# SubHarmonics_Main_Board_v1.net
KiCad netlist of a schematic drawn in EAGLE
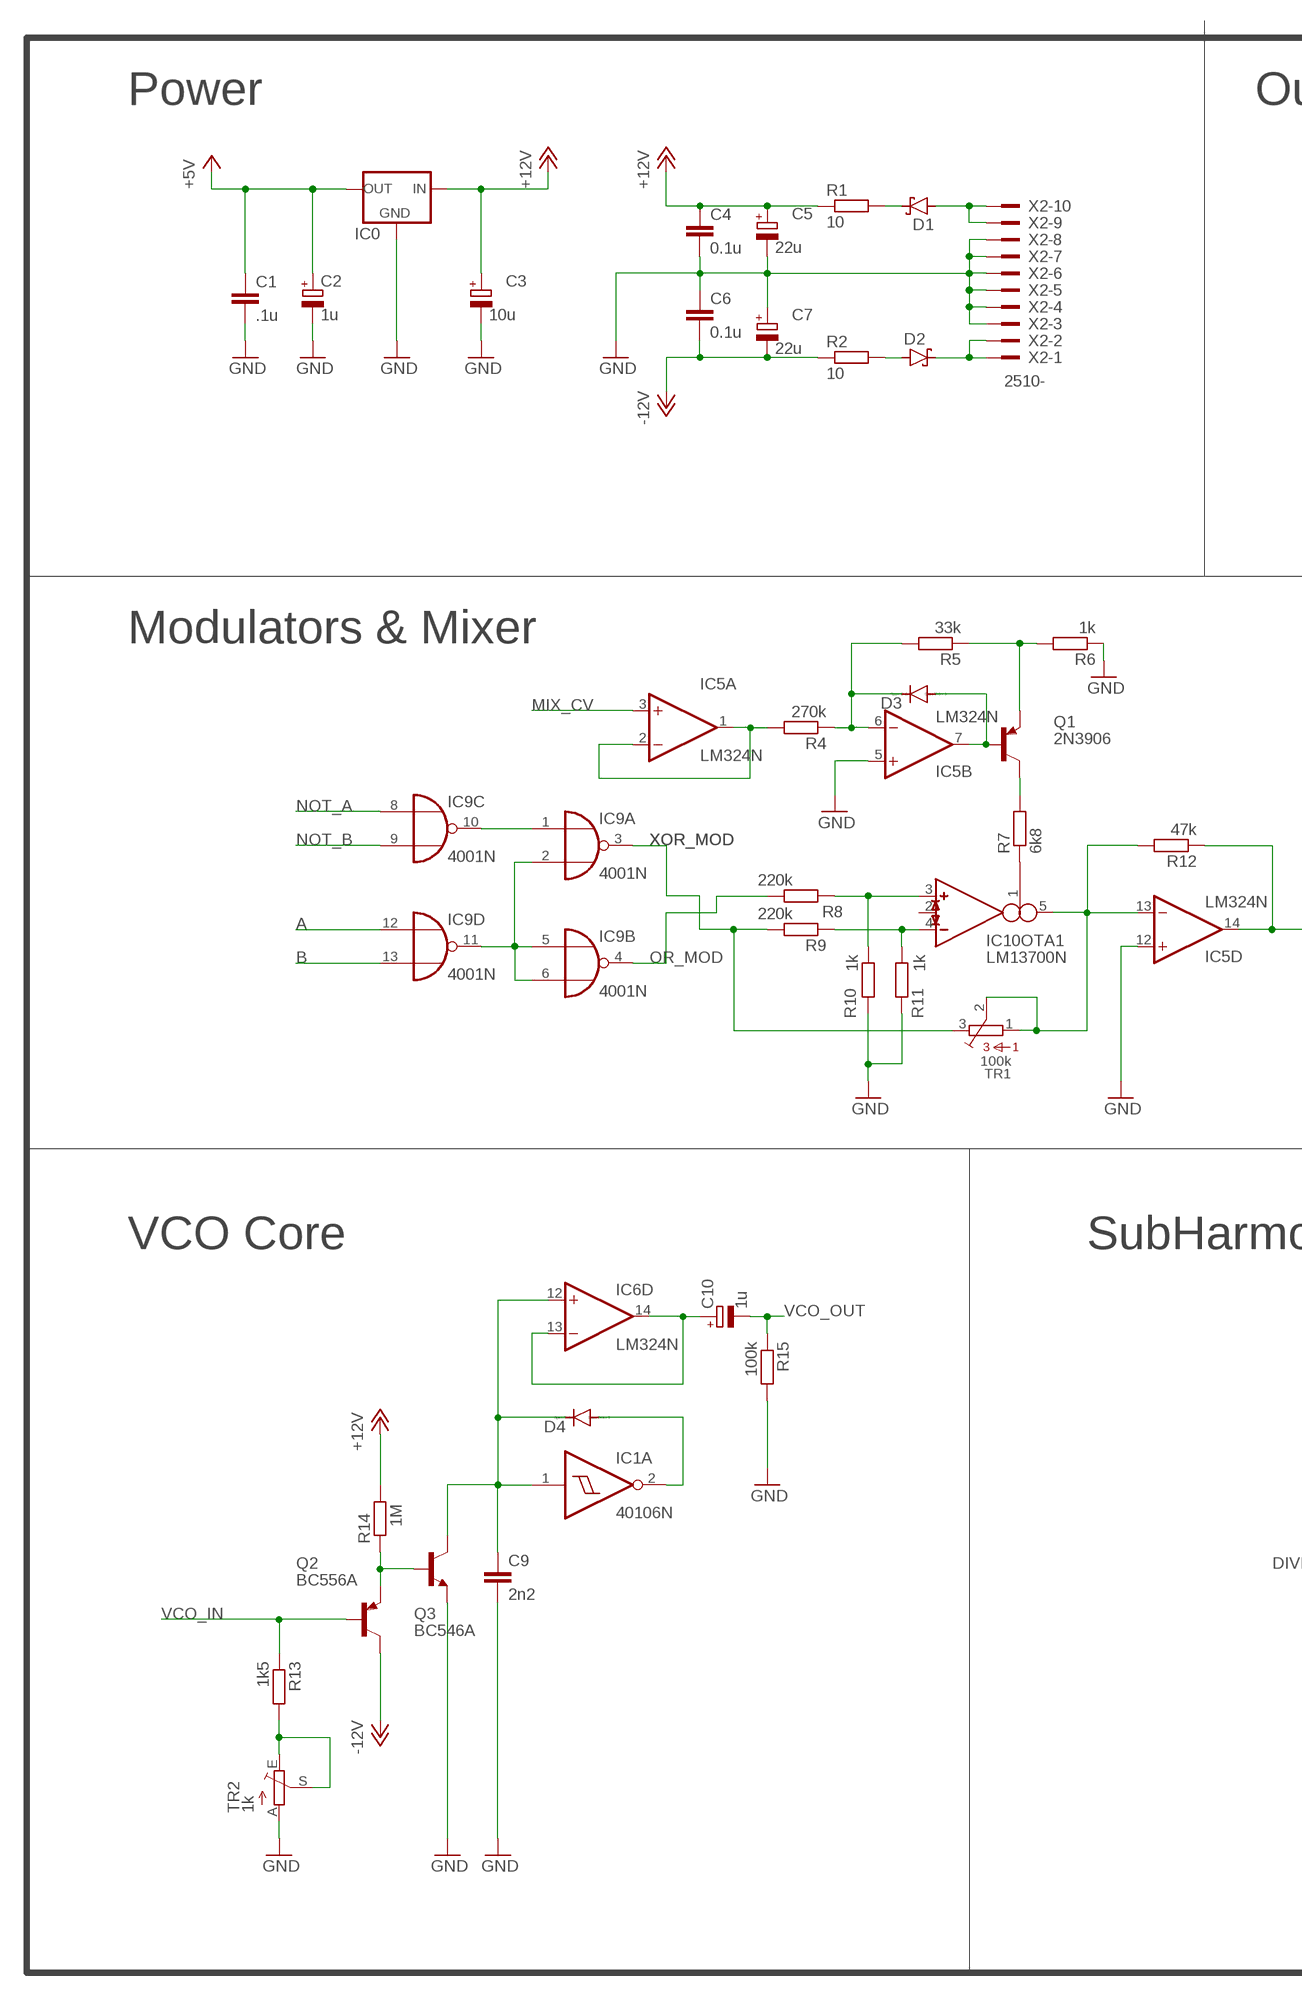
[diagram p0: schematic, sheet 1, part 1 of 2]
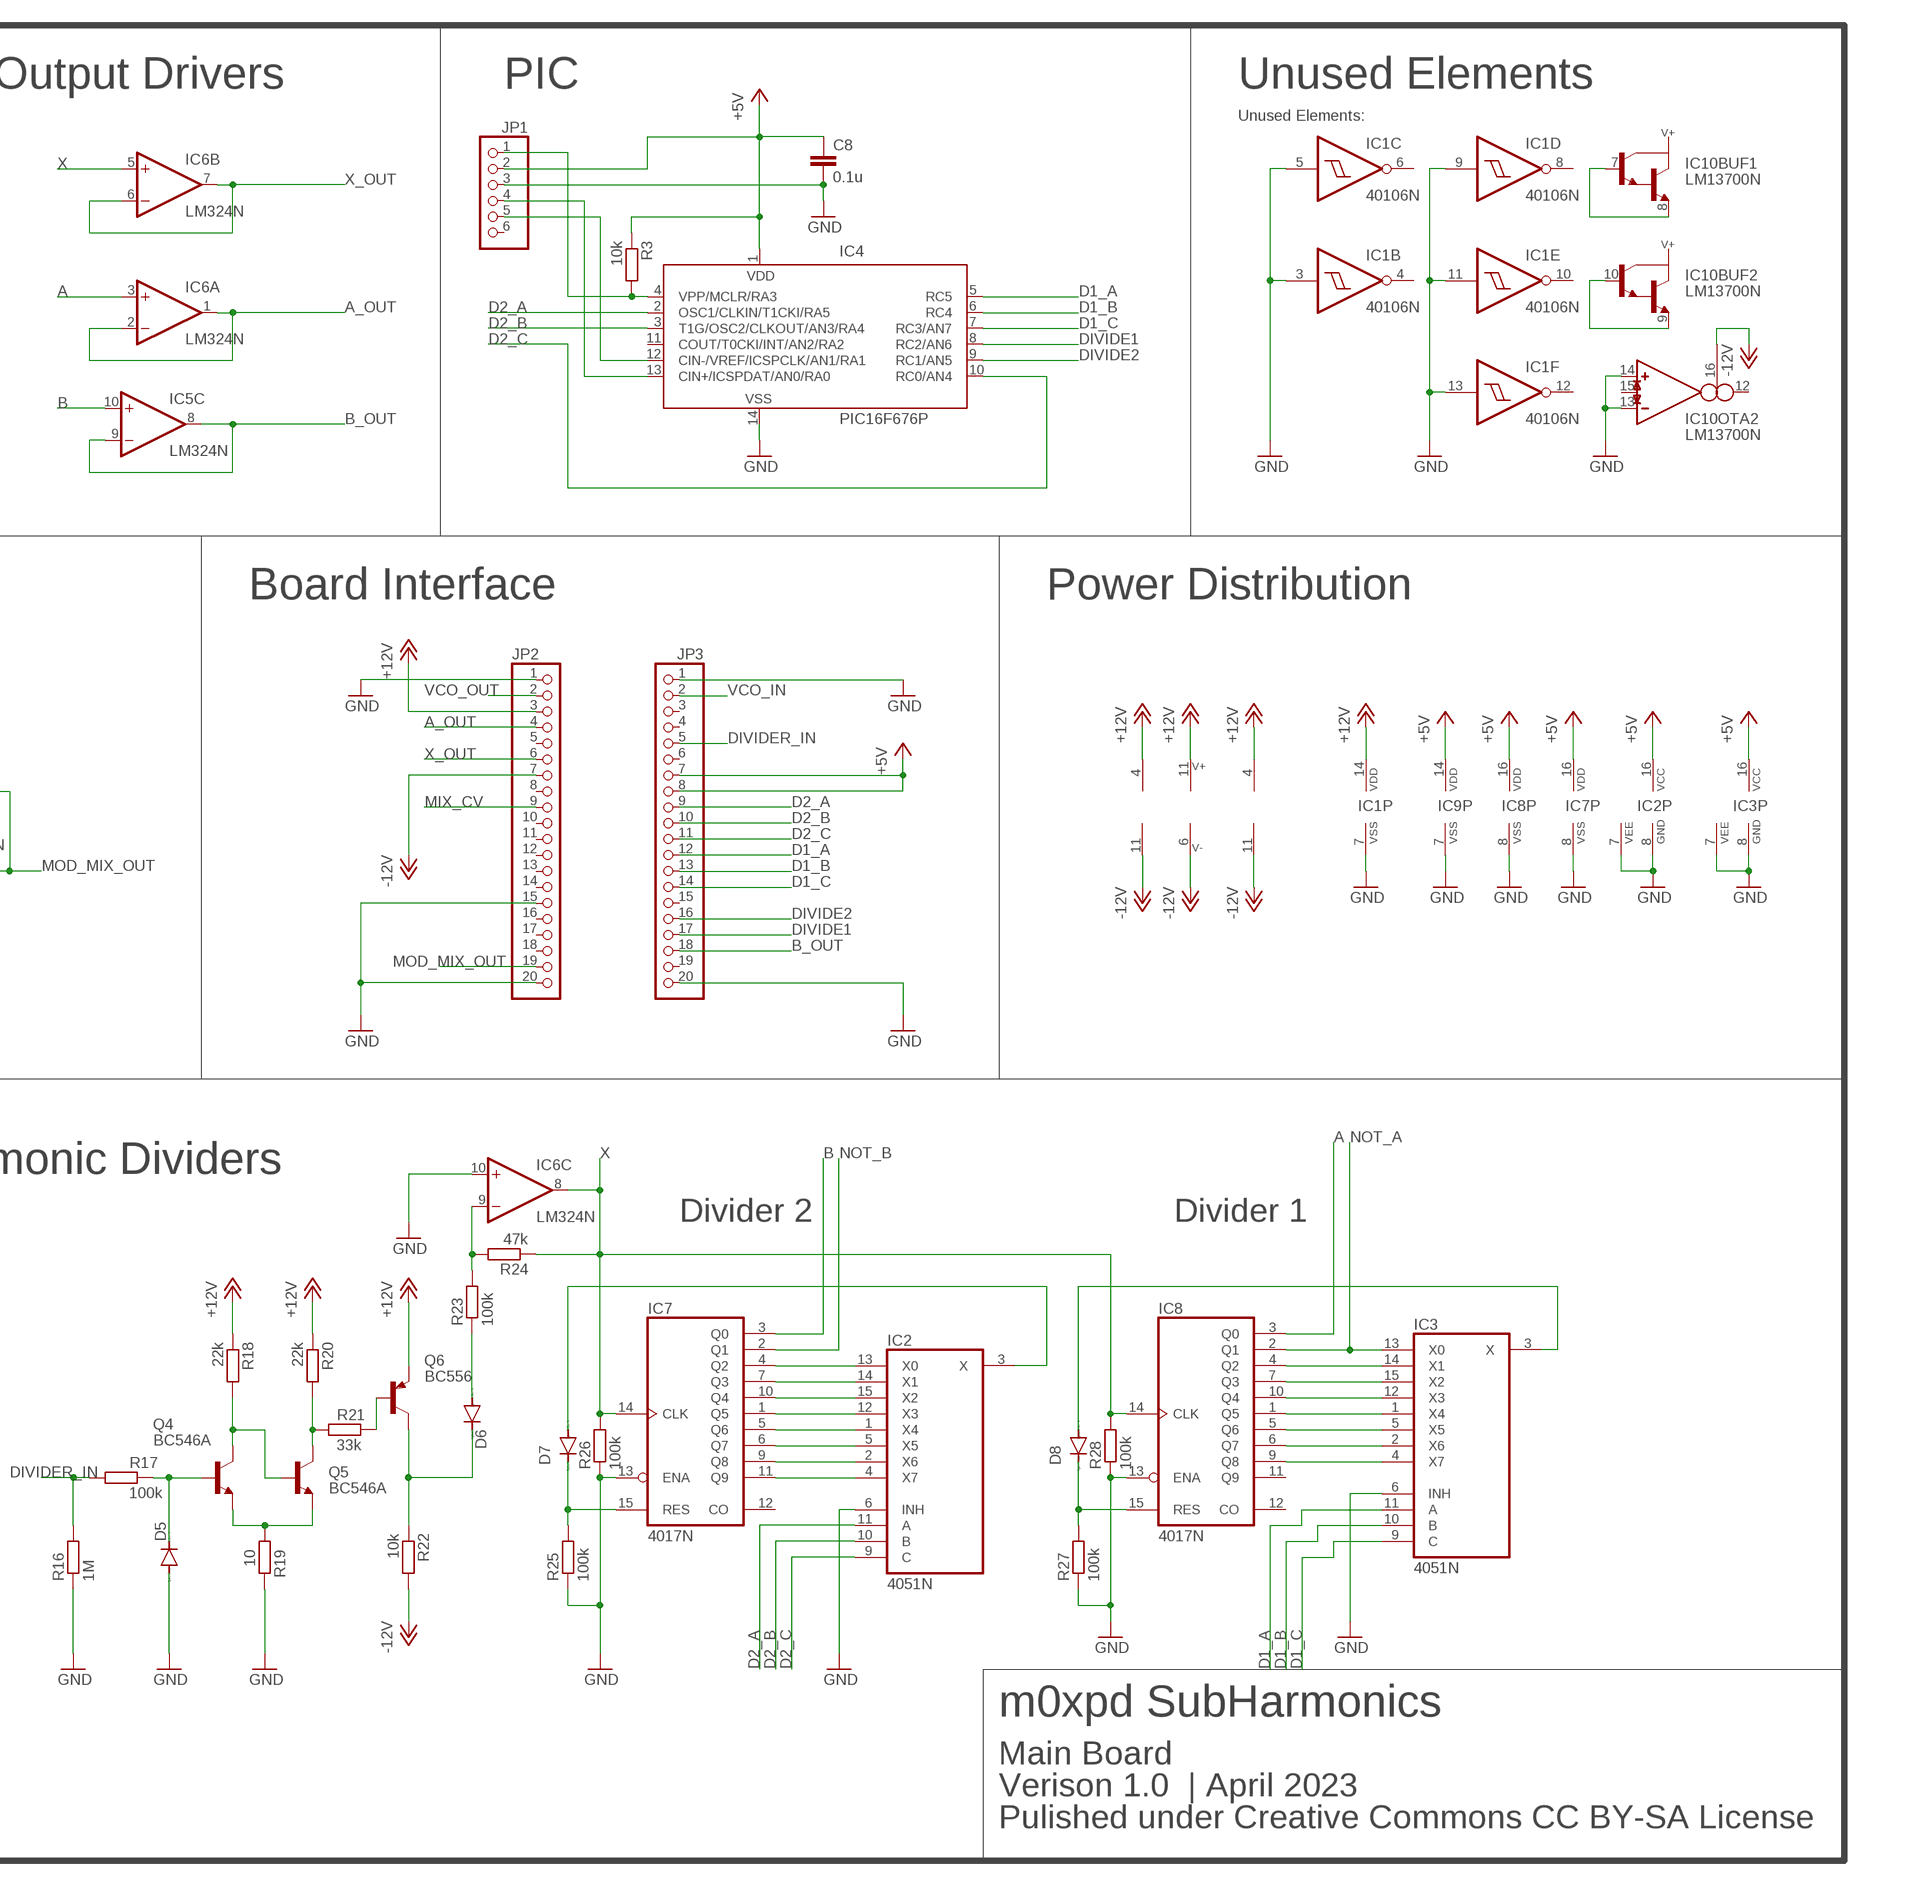
[diagram p1: schematic, sheet 1, part 2 of 2]

(export (version "E")
  (design (tool "Eeschema 10.0.6"))
  (components
    (comp (ref "C1")
      (value ".1u")
      (footprint "eagle-import:C050-025X075")
      (libsource (lib "eagle-import") (part "C-EU050-025X075"))
    )
    (comp (ref "C2")
      (value "1u")
      (footprint "eagle-import:E2,5-5")
      (libsource (lib "eagle-import") (part "CPOL-EUE2.5-5"))
    )
    (comp (ref "C3")
      (value "10u")
      (footprint "eagle-import:E2,5-5")
      (libsource (lib "eagle-import") (part "CPOL-EUE2.5-5"))
    )
    (comp (ref "C4")
      (value "0.1u")
      (footprint "eagle-import:C050-025X075")
      (libsource (lib "eagle-import") (part "C-EU050-025X075"))
    )
    (comp (ref "C5")
      (value "22u")
      (footprint "eagle-import:E2,5-5")
      (libsource (lib "eagle-import") (part "CPOL-EUE2.5-5"))
    )
    (comp (ref "C6")
      (value "0.1u")
      (footprint "eagle-import:C050-025X075")
      (libsource (lib "eagle-import") (part "C-EU050-025X075"))
    )
    (comp (ref "C7")
      (value "22u")
      (footprint "eagle-import:E2,5-5")
      (libsource (lib "eagle-import") (part "CPOL-EUE2.5-5"))
    )
    (comp (ref "C8")
      (value "0.1u")
      (footprint "eagle-import:C050-025X075")
      (libsource (lib "eagle-import") (part "C-EU050-025X075"))
    )
    (comp (ref "C9")
      (value "2n2")
      (footprint "eagle-import:C050-030X075")
      (libsource (lib "eagle-import") (part "C-EU050-030X075"))
    )
    (comp (ref "C10")
      (value "1u")
      (footprint "eagle-import:E2,5-5")
      (libsource (lib "eagle-import") (part "CPOL-EUE2.5-5"))
    )
    (comp (ref "D1")
      (value "SCHOTTKY-DIODEDO35-7")
      (footprint "eagle-import:DO35-7")
      (libsource (lib "eagle-import") (part "SCHOTTKY-DIODEDO35-7"))
    )
    (comp (ref "D2")
      (value "SCHOTTKY-DIODEDO35-7")
      (footprint "eagle-import:DO35-7")
      (libsource (lib "eagle-import") (part "SCHOTTKY-DIODEDO35-7"))
    )
    (comp (ref "D3")
      (value "1N4148DO35-7")
      (footprint "eagle-import:DO35-7")
      (libsource (lib "eagle-import") (part "1N4148DO35-7"))
    )
    (comp (ref "D4")
      (value "1N4148DO35-7")
      (footprint "eagle-import:DO35-7")
      (libsource (lib "eagle-import") (part "1N4148DO35-7"))
    )
    (comp (ref "D5")
      (value "1N4148DO35-7")
      (footprint "eagle-import:DO35-7")
      (libsource (lib "eagle-import") (part "1N4148DO35-7"))
    )
    (comp (ref "D6")
      (value "1N4148DO35-7")
      (footprint "eagle-import:DO35-7")
      (libsource (lib "eagle-import") (part "1N4148DO35-7"))
    )
    (comp (ref "D7")
      (value "1N4148DO35-7")
      (footprint "eagle-import:DO35-7")
      (libsource (lib "eagle-import") (part "1N4148DO35-7"))
    )
    (comp (ref "D8")
      (value "1N4148DO35-7")
      (footprint "eagle-import:DO35-7")
      (libsource (lib "eagle-import") (part "1N4148DO35-7"))
    )
    (comp (ref "IC0")
      (value "78LXX")
      (footprint "eagle-import:78LXX")
      (libsource (lib "eagle-import") (part "78LXX"))
    )
    (comp (ref "IC1")
      (value "40106N")
      (footprint "eagle-import:DIL14")
      (libsource (lib "eagle-import") (part "40106N"))
    )
    (comp (ref "IC2")
      (value "4051N")
      (footprint "eagle-import:DIL16")
      (libsource (lib "eagle-import") (part "4051N"))
    )
    (comp (ref "IC3")
      (value "4051N")
      (footprint "eagle-import:DIL16")
      (libsource (lib "eagle-import") (part "4051N"))
    )
    (comp (ref "IC4")
      (value "PIC16F676P")
      (footprint "eagle-import:DIL14")
      (fields (field (name "MF") "MICROCHIP") (field (name "MPN") "PIC16F676-I/P"))
      (libsource (lib "eagle-import") (part "PIC16F676P"))
    )
    (comp (ref "IC5")
      (value "LM324N")
      (footprint "eagle-import:DIL14")
      (libsource (lib "eagle-import") (part "LM324N"))
    )
    (comp (ref "IC6")
      (value "LM324N")
      (footprint "eagle-import:DIL14")
      (libsource (lib "eagle-import") (part "LM324N"))
    )
    (comp (ref "IC7")
      (value "4017N")
      (footprint "eagle-import:DIL16")
      (libsource (lib "eagle-import") (part "4017N"))
    )
    (comp (ref "IC8")
      (value "4017N")
      (footprint "eagle-import:DIL16")
      (libsource (lib "eagle-import") (part "4017N"))
    )
    (comp (ref "IC9")
      (value "4001N")
      (footprint "eagle-import:DIL14")
      (libsource (lib "eagle-import") (part "4001N"))
    )
    (comp (ref "IC10")
      (value "LM13700N")
      (footprint "eagle-import:DIL16")
      (libsource (lib "eagle-import") (part "LM13700N"))
    )
    (comp (ref "JP1")
      (value "PINHD-1X6")
      (footprint "eagle-import:1X06")
      (libsource (lib "eagle-import") (part "PINHD-1X6"))
    )
    (comp (ref "JP2")
      (value "PINHD-1X20")
      (footprint "eagle-import:1X20")
      (libsource (lib "eagle-import") (part "PINHD-1X20"))
    )
    (comp (ref "JP3")
      (value "PINHD-1X20")
      (footprint "eagle-import:1X20")
      (libsource (lib "eagle-import") (part "PINHD-1X20"))
    )
    (comp (ref "Q1")
      (value "2N3906")
      (footprint "eagle-import:TO92")
      (libsource (lib "eagle-import") (part "2N3906"))
    )
    (comp (ref "Q2")
      (value "BC556A")
      (footprint "eagle-import:TO92-EBC")
      (libsource (lib "eagle-import") (part "BC556A"))
    )
    (comp (ref "Q3")
      (value "BC546A")
      (footprint "eagle-import:TO92-EBC")
      (libsource (lib "eagle-import") (part "BC546A"))
    )
    (comp (ref "Q4")
      (value "BC546A")
      (footprint "eagle-import:TO92-EBC")
      (libsource (lib "eagle-import") (part "BC546A"))
    )
    (comp (ref "Q5")
      (value "BC546A")
      (footprint "eagle-import:TO92-EBC")
      (libsource (lib "eagle-import") (part "BC546A"))
    )
    (comp (ref "Q6")
      (value "BC556")
      (footprint "eagle-import:TO92-EBC")
      (libsource (lib "eagle-import") (part "BC556"))
    )
    (comp (ref "R1")
      (value "10")
      (footprint "eagle-import:0204_7")
      (libsource (lib "eagle-import") (part "R-EU_0204/7"))
    )
    (comp (ref "R2")
      (value "10")
      (footprint "eagle-import:0204_7")
      (libsource (lib "eagle-import") (part "R-EU_0204/7"))
    )
    (comp (ref "R3")
      (value "10k")
      (footprint "eagle-import:0204_7")
      (libsource (lib "eagle-import") (part "R-EU_0204/7"))
    )
    (comp (ref "R4")
      (value "270k")
      (footprint "eagle-import:0204_7")
      (libsource (lib "eagle-import") (part "R-EU_0204/7"))
    )
    (comp (ref "R5")
      (value "33k")
      (footprint "eagle-import:0204_7")
      (libsource (lib "eagle-import") (part "R-EU_0204/7"))
    )
    (comp (ref "R6")
      (value "1k")
      (footprint "eagle-import:0204_7")
      (libsource (lib "eagle-import") (part "R-EU_0204/7"))
    )
    (comp (ref "R7")
      (value "6k8")
      (footprint "eagle-import:0204_7")
      (libsource (lib "eagle-import") (part "R-EU_0204/7"))
    )
    (comp (ref "R8")
      (value "220k")
      (footprint "eagle-import:0204_7")
      (libsource (lib "eagle-import") (part "R-EU_0204/7"))
    )
    (comp (ref "R9")
      (value "220k")
      (footprint "eagle-import:0204_7")
      (libsource (lib "eagle-import") (part "R-EU_0204/7"))
    )
    (comp (ref "R10")
      (value "1k")
      (footprint "eagle-import:0204_7")
      (libsource (lib "eagle-import") (part "R-EU_0204/7"))
    )
    (comp (ref "R11")
      (value "1k")
      (footprint "eagle-import:0204_7")
      (libsource (lib "eagle-import") (part "R-EU_0204/7"))
    )
    (comp (ref "R12")
      (value "47k")
      (footprint "eagle-import:0204_7")
      (libsource (lib "eagle-import") (part "R-EU_0204/7"))
    )
    (comp (ref "R13")
      (value "1k5")
      (footprint "eagle-import:0204_7")
      (libsource (lib "eagle-import") (part "R-EU_0204/7"))
    )
    (comp (ref "R14")
      (value "1M")
      (footprint "eagle-import:0204_7")
      (libsource (lib "eagle-import") (part "R-EU_0204/7"))
    )
    (comp (ref "R15")
      (value "100k")
      (footprint "eagle-import:0204_7")
      (libsource (lib "eagle-import") (part "R-EU_0204/7"))
    )
    (comp (ref "R16")
      (value "1M")
      (footprint "eagle-import:0204_7")
      (libsource (lib "eagle-import") (part "R-EU_0204/7"))
    )
    (comp (ref "R17")
      (value "100k")
      (footprint "eagle-import:0204_7")
      (libsource (lib "eagle-import") (part "R-EU_0204/7"))
    )
    (comp (ref "R18")
      (value "22k")
      (footprint "eagle-import:0204_7")
      (libsource (lib "eagle-import") (part "R-EU_0204/7"))
    )
    (comp (ref "R19")
      (value "10")
      (footprint "eagle-import:0204_7")
      (libsource (lib "eagle-import") (part "R-EU_0204/7"))
    )
    (comp (ref "R20")
      (value "22k")
      (footprint "eagle-import:0204_7")
      (libsource (lib "eagle-import") (part "R-EU_0204/7"))
    )
    (comp (ref "R21")
      (value "33k")
      (footprint "eagle-import:0204_7")
      (libsource (lib "eagle-import") (part "R-EU_0204/7"))
    )
    (comp (ref "R22")
      (value "10k")
      (footprint "eagle-import:0204_7")
      (libsource (lib "eagle-import") (part "R-EU_0204/7"))
    )
    (comp (ref "R23")
      (value "100k")
      (footprint "eagle-import:0204_7")
      (libsource (lib "eagle-import") (part "R-EU_0204/7"))
    )
    (comp (ref "R24")
      (value "47k")
      (footprint "eagle-import:0204_7")
      (libsource (lib "eagle-import") (part "R-EU_0204/7"))
    )
    (comp (ref "R25")
      (value "100k")
      (footprint "eagle-import:0204_7")
      (libsource (lib "eagle-import") (part "R-EU_0204/7"))
    )
    (comp (ref "R26")
      (value "100k")
      (footprint "eagle-import:0204_7")
      (libsource (lib "eagle-import") (part "R-EU_0204/7"))
    )
    (comp (ref "R27")
      (value "100k")
      (footprint "eagle-import:0204_7")
      (libsource (lib "eagle-import") (part "R-EU_0204/7"))
    )
    (comp (ref "R28")
      (value "100k")
      (footprint "eagle-import:0204_7")
      (libsource (lib "eagle-import") (part "R-EU_0204/7"))
    )
    (comp (ref "TR1")
      (value "100k")
      (footprint "eagle-import:BOURNS_3362P_TRIMMER")
      (libsource (lib "eagle-import") (part "BOURNS_3362P_TRIMMERP"))
    )
    (comp (ref "TR2")
      (value "1k")
      (footprint "eagle-import:B64Y")
      (libsource (lib "eagle-import") (part "TRIM_EU-B64Y"))
    )
    (comp (ref "X2")
      (value "2510-")
      (footprint "eagle-import:PAK100_2500-10")
      (fields (field (name "MF") "3M") (field (name "MPN") "2510-6002UB"))
      (libsource (lib "eagle-import") (part "2510-"))
    )
  )
  (nets
    (net (code "1") (name "+5V") (class "Default")
      (node (ref "C1") (pin "1") (pinfunction "1_1") (pintype "passive"))
      (node (ref "C2") (pin "+") (pinfunction "+_+") (pintype "passive"))
      (node (ref "C8") (pin "1") (pinfunction "1_1") (pintype "passive"))
      (node (ref "IC0") (pin "OUT") (pinfunction "OUT_OUT") (pintype "passive"))
      (node (ref "IC2") (pin "16") (pinfunction "VCC_16") (pintype "power_in"))
      (node (ref "IC3") (pin "16") (pinfunction "VCC_16") (pintype "power_in"))
      (node (ref "IC4") (pin "1") (pinfunction "VDD_1") (pintype "power_in"))
      (node (ref "IC7") (pin "16") (pinfunction "VDD_16") (pintype "power_in"))
      (node (ref "IC8") (pin "16") (pinfunction "VDD_16") (pintype "power_in"))
      (node (ref "IC9") (pin "14") (pinfunction "VDD_14") (pintype "power_in"))
      (node (ref "JP1") (pin "2") (pinfunction "2_2") (pintype "passive"))
      (node (ref "JP3") (pin "7") (pinfunction "7_7") (pintype "passive"))
      (node (ref "JP3") (pin "8") (pinfunction "8_8") (pintype "passive"))
      (node (ref "R3") (pin "1") (pinfunction "1_1") (pintype "passive"))
    )
    (net (code "2") (name "+12V") (class "Default")
      (node (ref "C3") (pin "+") (pinfunction "+_+") (pintype "passive"))
      (node (ref "C4") (pin "1") (pinfunction "1_1") (pintype "passive"))
      (node (ref "C5") (pin "+") (pinfunction "+_+") (pintype "passive"))
      (node (ref "IC0") (pin "IN") (pinfunction "IN_IN") (pintype "input"))
      (node (ref "IC1") (pin "14") (pinfunction "VDD_14") (pintype "power_in"))
      (node (ref "IC10") (pin "11") (pinfunction "V+_11") (pintype "power_in"))
      (node (ref "IC5") (pin "4") (pinfunction "V+_4") (pintype "power_in"))
      (node (ref "IC6") (pin "4") (pinfunction "V+_4") (pintype "power_in"))
      (node (ref "JP2") (pin "3") (pinfunction "3_3") (pintype "passive"))
      (node (ref "Q6") (pin "E") (pinfunction "E_E") (pintype "passive"))
      (node (ref "R1") (pin "1") (pinfunction "1_1") (pintype "passive"))
      (node (ref "R14") (pin "2") (pinfunction "2_2") (pintype "passive"))
      (node (ref "R18") (pin "1") (pinfunction "1_1") (pintype "passive"))
      (node (ref "R20") (pin "1") (pinfunction "1_1") (pintype "passive"))
    )
    (net (code "3") (name "-12V") (class "Default")
      (node (ref "C6") (pin "2") (pinfunction "2_2") (pintype "passive"))
      (node (ref "C7") (pin "-") (pinfunction "-_-") (pintype "passive"))
      (node (ref "IC10") (pin "16") (pinfunction "I_BIAS_16") (pintype "input"))
      (node (ref "IC10") (pin "6") (pinfunction "V-_6") (pintype "power_in"))
      (node (ref "IC5") (pin "11") (pinfunction "V-_11") (pintype "power_in"))
      (node (ref "IC6") (pin "11") (pinfunction "V-_11") (pintype "power_in"))
      (node (ref "JP2") (pin "7") (pinfunction "7_7") (pintype "passive"))
      (node (ref "Q2") (pin "C") (pinfunction "C_C") (pintype "passive"))
      (node (ref "R2") (pin "1") (pinfunction "1_1") (pintype "passive"))
      (node (ref "R22") (pin "2") (pinfunction "2_2") (pintype "passive"))
    )
    (net (code "4") (name "/A") (class "Default")
      (node (ref "IC6") (pin "3") (pinfunction "+IN_3") (pintype "input"))
      (node (ref "IC8") (pin "3") (pinfunction "Q0_3") (pintype "output"))
      (node (ref "IC9") (pin "12") (pinfunction "I0_12") (pintype "input"))
    )
    (net (code "5") (name "/A_OUT") (class "Default")
      (node (ref "IC6") (pin "1") (pinfunction "OUT_1") (pintype "output"))
      (node (ref "IC6") (pin "2") (pinfunction "-IN_2") (pintype "input"))
      (node (ref "JP2") (pin "4") (pinfunction "4_4") (pintype "passive"))
    )
    (net (code "6") (name "/B") (class "Default")
      (node (ref "IC5") (pin "10") (pinfunction "+IN_10") (pintype "input"))
      (node (ref "IC7") (pin "3") (pinfunction "Q0_3") (pintype "output"))
      (node (ref "IC9") (pin "13") (pinfunction "I1_13") (pintype "input"))
    )
    (net (code "7") (name "/B_OUT") (class "Default")
      (node (ref "IC5") (pin "8") (pinfunction "OUT_8") (pintype "output"))
      (node (ref "IC5") (pin "9") (pinfunction "-IN_9") (pintype "input"))
      (node (ref "JP3") (pin "18") (pinfunction "18_18") (pintype "passive"))
    )
    (net (code "8") (name "/D1_A") (class "Default")
      (node (ref "IC3") (pin "11") (pinfunction "A_11") (pintype "input"))
      (node (ref "IC4") (pin "5") (pinfunction "RC5_5") (pintype "bidirectional"))
      (node (ref "JP3") (pin "12") (pinfunction "12_12") (pintype "passive"))
    )
    (net (code "9") (name "/D1_B") (class "Default")
      (node (ref "IC3") (pin "10") (pinfunction "B_10") (pintype "input"))
      (node (ref "IC4") (pin "6") (pinfunction "RC4_6") (pintype "bidirectional"))
      (node (ref "JP3") (pin "13") (pinfunction "13_13") (pintype "passive"))
    )
    (net (code "10") (name "/D1_C") (class "Default")
      (node (ref "IC3") (pin "9") (pinfunction "C_9") (pintype "input"))
      (node (ref "IC4") (pin "7") (pinfunction "RC3/AN7_7") (pintype "bidirectional"))
      (node (ref "JP3") (pin "14") (pinfunction "14_14") (pintype "passive"))
    )
    (net (code "11") (name "/D2_A") (class "Default")
      (node (ref "IC2") (pin "11") (pinfunction "A_11") (pintype "input"))
      (node (ref "IC4") (pin "2") (pinfunction "OSC1/CLKIN/T1CKI/RA5_2") (pintype "bidirectional"))
      (node (ref "JP3") (pin "9") (pinfunction "9_9") (pintype "passive"))
    )
    (net (code "12") (name "/D2_B") (class "Default")
      (node (ref "IC2") (pin "10") (pinfunction "B_10") (pintype "input"))
      (node (ref "IC4") (pin "3") (pinfunction "T1G/OSC2/CLKOUT/AN3/RA4_3") (pintype "bidirectional"))
      (node (ref "JP3") (pin "10") (pinfunction "10_10") (pintype "passive"))
    )
    (net (code "13") (name "/D2_C") (class "Default")
      (node (ref "IC2") (pin "9") (pinfunction "C_9") (pintype "input"))
      (node (ref "IC4") (pin "10") (pinfunction "RC0/AN4_10") (pintype "bidirectional"))
      (node (ref "JP3") (pin "11") (pinfunction "11_11") (pintype "passive"))
    )
    (net (code "14") (name "/DIVIDE1") (class "Default")
      (node (ref "IC4") (pin "8") (pinfunction "RC2/AN6_8") (pintype "bidirectional"))
      (node (ref "JP3") (pin "17") (pinfunction "17_17") (pintype "passive"))
    )
    (net (code "15") (name "/DIVIDE2") (class "Default")
      (node (ref "IC4") (pin "9") (pinfunction "RC1/AN5_9") (pintype "bidirectional"))
      (node (ref "JP3") (pin "16") (pinfunction "16_16") (pintype "passive"))
    )
    (net (code "16") (name "/DIVIDER_IN") (class "Default")
      (node (ref "JP3") (pin "5") (pinfunction "5_5") (pintype "passive"))
      (node (ref "R16") (pin "2") (pinfunction "2_2") (pintype "passive"))
      (node (ref "R17") (pin "1") (pinfunction "1_1") (pintype "passive"))
    )
    (net (code "17") (name "/MIX_CV") (class "Default")
      (node (ref "IC5") (pin "3") (pinfunction "+IN_3") (pintype "input"))
      (node (ref "JP2") (pin "9") (pinfunction "9_9") (pintype "passive"))
    )
    (net (code "18") (name "/MOD_MIX_OUT") (class "Default")
      (node (ref "IC5") (pin "14") (pinfunction "OUT_14") (pintype "output"))
      (node (ref "JP2") (pin "19") (pinfunction "19_19") (pintype "passive"))
      (node (ref "R12") (pin "1") (pinfunction "1_1") (pintype "passive"))
    )
    (net (code "19") (name "/NOT_A") (class "Default")
      (node (ref "IC3") (pin "13") (pinfunction "X0_13") (pintype "bidirectional"))
      (node (ref "IC8") (pin "2") (pinfunction "Q1_2") (pintype "output"))
      (node (ref "IC9") (pin "8") (pinfunction "I0_8") (pintype "input"))
    )
    (net (code "20") (name "/NOT_B") (class "Default")
      (node (ref "IC7") (pin "2") (pinfunction "Q1_2") (pintype "output"))
      (node (ref "IC9") (pin "9") (pinfunction "I1_9") (pintype "input"))
    )
    (net (code "21") (name "/OR_MOD") (class "Default")
      (node (ref "IC9") (pin "4") (pinfunction "O_4") (pintype "output"))
      (node (ref "R8") (pin "2") (pinfunction "2_2") (pintype "passive"))
    )
    (net (code "22") (name "/VCO_IN") (class "Default")
      (node (ref "JP3") (pin "2") (pinfunction "2_2") (pintype "passive"))
      (node (ref "Q2") (pin "B") (pinfunction "B_B") (pintype "passive"))
      (node (ref "R13") (pin "1") (pinfunction "1_1") (pintype "passive"))
    )
    (net (code "23") (name "/VCO_OUT") (class "Default")
      (node (ref "C10") (pin "-") (pinfunction "-_-") (pintype "passive"))
      (node (ref "JP2") (pin "2") (pinfunction "2_2") (pintype "passive"))
      (node (ref "R15") (pin "1") (pinfunction "1_1") (pintype "passive"))
    )
    (net (code "24") (name "/X") (class "Default")
      (node (ref "IC6") (pin "5") (pinfunction "+IN_5") (pintype "input"))
      (node (ref "IC6") (pin "8") (pinfunction "OUT_8") (pintype "output"))
      (node (ref "IC7") (pin "14") (pinfunction "CLK_14") (pintype "input"))
      (node (ref "IC8") (pin "14") (pinfunction "CLK_14") (pintype "input"))
      (node (ref "R24") (pin "1") (pinfunction "1_1") (pintype "passive"))
      (node (ref "R26") (pin "2") (pinfunction "2_2") (pintype "passive"))
      (node (ref "R28") (pin "2") (pinfunction "2_2") (pintype "passive"))
    )
    (net (code "25") (name "/XOR_MOD") (class "Default")
      (node (ref "IC9") (pin "3") (pinfunction "O_3") (pintype "output"))
      (node (ref "R9") (pin "2") (pinfunction "2_2") (pintype "passive"))
      (node (ref "TR1") (pin "3") (pinfunction "3_3") (pintype "passive"))
    )
    (net (code "26") (name "/X_OUT") (class "Default")
      (node (ref "IC6") (pin "6") (pinfunction "-IN_6") (pintype "input"))
      (node (ref "IC6") (pin "7") (pinfunction "OUT_7") (pintype "output"))
      (node (ref "JP2") (pin "6") (pinfunction "6_6") (pintype "passive"))
    )
    (net (code "27") (name "GND") (class "Default")
      (node (ref "C1") (pin "2") (pinfunction "2_2") (pintype "passive"))
      (node (ref "C2") (pin "-") (pinfunction "-_-") (pintype "passive"))
      (node (ref "C3") (pin "-") (pinfunction "-_-") (pintype "passive"))
      (node (ref "C4") (pin "2") (pinfunction "2_2") (pintype "passive"))
      (node (ref "C5") (pin "-") (pinfunction "-_-") (pintype "passive"))
      (node (ref "C6") (pin "1") (pinfunction "1_1") (pintype "passive"))
      (node (ref "C7") (pin "+") (pinfunction "+_+") (pintype "passive"))
      (node (ref "C8") (pin "2") (pinfunction "2_2") (pintype "passive"))
      (node (ref "C9") (pin "2") (pinfunction "2_2") (pintype "passive"))
      (node (ref "D5") (pin "A") (pinfunction "A_A") (pintype "passive"))
      (node (ref "IC0") (pin "GND") (pinfunction "GND_GND") (pintype "input"))
      (node (ref "IC1") (pin "11") (pinfunction "I_11") (pintype "input"))
      (node (ref "IC1") (pin "13") (pinfunction "I_13") (pintype "input"))
      (node (ref "IC1") (pin "3") (pinfunction "I_3") (pintype "input"))
      (node (ref "IC1") (pin "5") (pinfunction "I_5") (pintype "input"))
      (node (ref "IC1") (pin "7") (pinfunction "VSS_7") (pintype "power_in"))
      (node (ref "IC1") (pin "9") (pinfunction "I_9") (pintype "input"))
      (node (ref "IC10") (pin "13") (pinfunction "IN_N_13") (pintype "input"))
      (node (ref "IC10") (pin "14") (pinfunction "IN_P_14") (pintype "input"))
      (node (ref "IC2") (pin "6") (pinfunction "INH_6") (pintype "input"))
      (node (ref "IC2") (pin "7") (pinfunction "VEE_7") (pintype "power_in"))
      (node (ref "IC2") (pin "8") (pinfunction "GND_8") (pintype "power_in"))
      (node (ref "IC3") (pin "6") (pinfunction "INH_6") (pintype "input"))
      (node (ref "IC3") (pin "7") (pinfunction "VEE_7") (pintype "power_in"))
      (node (ref "IC3") (pin "8") (pinfunction "GND_8") (pintype "power_in"))
      (node (ref "IC4") (pin "14") (pinfunction "VSS_14") (pintype "power_in"))
      (node (ref "IC5") (pin "12") (pinfunction "+IN_12") (pintype "input"))
      (node (ref "IC5") (pin "5") (pinfunction "+IN_5") (pintype "input"))
      (node (ref "IC6") (pin "10") (pinfunction "+IN_10") (pintype "input"))
      (node (ref "IC7") (pin "13") (pinfunction "ENA_13") (pintype "input"))
      (node (ref "IC7") (pin "8") (pinfunction "VSS_8") (pintype "power_in"))
      (node (ref "IC8") (pin "13") (pinfunction "ENA_13") (pintype "input"))
      (node (ref "IC8") (pin "8") (pinfunction "VSS_8") (pintype "power_in"))
      (node (ref "IC9") (pin "7") (pinfunction "VSS_7") (pintype "power_in"))
      (node (ref "JP1") (pin "3") (pinfunction "3_3") (pintype "passive"))
      (node (ref "JP2") (pin "1") (pinfunction "1_1") (pintype "passive"))
      (node (ref "JP2") (pin "15") (pinfunction "15_15") (pintype "passive"))
      (node (ref "JP2") (pin "20") (pinfunction "20_20") (pintype "passive"))
      (node (ref "JP3") (pin "1") (pinfunction "1_1") (pintype "passive"))
      (node (ref "JP3") (pin "20") (pinfunction "20_20") (pintype "passive"))
      (node (ref "Q3") (pin "E") (pinfunction "E_E") (pintype "passive"))
      (node (ref "R10") (pin "2") (pinfunction "2_2") (pintype "passive"))
      (node (ref "R11") (pin "2") (pinfunction "2_2") (pintype "passive"))
      (node (ref "R15") (pin "2") (pinfunction "2_2") (pintype "passive"))
      (node (ref "R16") (pin "1") (pinfunction "1_1") (pintype "passive"))
      (node (ref "R19") (pin "2") (pinfunction "2_2") (pintype "passive"))
      (node (ref "R25") (pin "1") (pinfunction "1_1") (pintype "passive"))
      (node (ref "R26") (pin "1") (pinfunction "1_1") (pintype "passive"))
      (node (ref "R27") (pin "1") (pinfunction "1_1") (pintype "passive"))
      (node (ref "R28") (pin "1") (pinfunction "1_1") (pintype "passive"))
      (node (ref "R6") (pin "1") (pinfunction "1_1") (pintype "passive"))
      (node (ref "TR2") (pin "A") (pinfunction "A_A") (pintype "passive"))
      (node (ref "X2") (pin "3") (pinfunction "KL_3") (pintype "passive"))
      (node (ref "X2") (pin "4") (pinfunction "KL_4") (pintype "passive"))
      (node (ref "X2") (pin "5") (pinfunction "KL_5") (pintype "passive"))
      (node (ref "X2") (pin "6") (pinfunction "KL_6") (pintype "passive"))
      (node (ref "X2") (pin "7") (pinfunction "KL_7") (pintype "passive"))
      (node (ref "X2") (pin "8") (pinfunction "KL_8") (pintype "passive"))
    )
    (net (code "28") (name "Net-(D1-PadC)") (class "Default")
      (node (ref "D1") (pin "C") (pinfunction "C_C") (pintype "passive"))
      (node (ref "R1") (pin "2") (pinfunction "2_2") (pintype "passive"))
    )
    (net (code "29") (name "Net-(D2-PadA)") (class "Default")
      (node (ref "D2") (pin "A") (pinfunction "A_A") (pintype "passive"))
      (node (ref "R2") (pin "2") (pinfunction "2_2") (pintype "passive"))
    )
    (net (code "30") (name "Net-(D5-PadC)") (class "Default")
      (node (ref "D5") (pin "C") (pinfunction "C_C") (pintype "passive"))
      (node (ref "Q4") (pin "B") (pinfunction "B_B") (pintype "passive"))
      (node (ref "R17") (pin "2") (pinfunction "2_2") (pintype "passive"))
    )
    (net (code "31") (name "Net-(D6-PadA)") (class "Default")
      (node (ref "D6") (pin "A") (pinfunction "A_A") (pintype "passive"))
      (node (ref "R23") (pin "1") (pinfunction "1_1") (pintype "passive"))
    )
    (net (code "32") (name "Net-(D6-PadC)") (class "Default")
      (node (ref "D6") (pin "C") (pinfunction "C_C") (pintype "passive"))
      (node (ref "Q6") (pin "C") (pinfunction "C_C") (pintype "passive"))
      (node (ref "R22") (pin "1") (pinfunction "1_1") (pintype "passive"))
    )
    (net (code "33") (name "Net-(IC1A-I)") (class "Default")
      (node (ref "C9") (pin "1") (pinfunction "1_1") (pintype "passive"))
      (node (ref "D4") (pin "C") (pinfunction "C_C") (pintype "passive"))
      (node (ref "IC1") (pin "1") (pinfunction "I_1") (pintype "input"))
      (node (ref "IC6") (pin "12") (pinfunction "+IN_12") (pintype "input"))
      (node (ref "Q3") (pin "C") (pinfunction "C_C") (pintype "passive"))
    )
    (net (code "34") (name "Net-(IC1A-O)") (class "Default")
      (node (ref "D4") (pin "A") (pinfunction "A_A") (pintype "passive"))
      (node (ref "IC1") (pin "2") (pinfunction "O_2") (pintype "output"))
    )
    (net (code "35") (name "Net-(IC2A-X)") (class "Default")
      (node (ref "D7") (pin "A") (pinfunction "A_A") (pintype "passive"))
      (node (ref "IC2") (pin "3") (pinfunction "X_3") (pintype "bidirectional"))
    )
    (net (code "36") (name "Net-(IC2A-X0)") (class "Default")
      (node (ref "IC2") (pin "13") (pinfunction "X0_13") (pintype "bidirectional"))
      (node (ref "IC7") (pin "4") (pinfunction "Q2_4") (pintype "output"))
    )
    (net (code "37") (name "Net-(IC2A-X1)") (class "Default")
      (node (ref "IC2") (pin "14") (pinfunction "X1_14") (pintype "bidirectional"))
      (node (ref "IC7") (pin "7") (pinfunction "Q3_7") (pintype "output"))
    )
    (net (code "38") (name "Net-(IC2A-X2)") (class "Default")
      (node (ref "IC2") (pin "15") (pinfunction "X2_15") (pintype "bidirectional"))
      (node (ref "IC7") (pin "10") (pinfunction "Q4_10") (pintype "output"))
    )
    (net (code "39") (name "Net-(IC2A-X3)") (class "Default")
      (node (ref "IC2") (pin "12") (pinfunction "X3_12") (pintype "bidirectional"))
      (node (ref "IC7") (pin "1") (pinfunction "Q5_1") (pintype "output"))
    )
    (net (code "40") (name "Net-(IC2A-X4)") (class "Default")
      (node (ref "IC2") (pin "1") (pinfunction "X4_1") (pintype "bidirectional"))
      (node (ref "IC7") (pin "5") (pinfunction "Q6_5") (pintype "output"))
    )
    (net (code "41") (name "Net-(IC2A-X5)") (class "Default")
      (node (ref "IC2") (pin "5") (pinfunction "X5_5") (pintype "bidirectional"))
      (node (ref "IC7") (pin "6") (pinfunction "Q7_6") (pintype "output"))
    )
    (net (code "42") (name "Net-(IC2A-X6)") (class "Default")
      (node (ref "IC2") (pin "2") (pinfunction "X6_2") (pintype "bidirectional"))
      (node (ref "IC7") (pin "9") (pinfunction "Q8_9") (pintype "output"))
    )
    (net (code "43") (name "Net-(IC2A-X7)") (class "Default")
      (node (ref "IC2") (pin "4") (pinfunction "X7_4") (pintype "bidirectional"))
      (node (ref "IC7") (pin "11") (pinfunction "Q9_11") (pintype "output"))
    )
    (net (code "44") (name "Net-(IC3A-X)") (class "Default")
      (node (ref "D8") (pin "A") (pinfunction "A_A") (pintype "passive"))
      (node (ref "IC3") (pin "3") (pinfunction "X_3") (pintype "bidirectional"))
    )
    (net (code "45") (name "Net-(IC3A-X1)") (class "Default")
      (node (ref "IC3") (pin "14") (pinfunction "X1_14") (pintype "bidirectional"))
      (node (ref "IC8") (pin "4") (pinfunction "Q2_4") (pintype "output"))
    )
    (net (code "46") (name "Net-(IC3A-X2)") (class "Default")
      (node (ref "IC3") (pin "15") (pinfunction "X2_15") (pintype "bidirectional"))
      (node (ref "IC8") (pin "7") (pinfunction "Q3_7") (pintype "output"))
    )
    (net (code "47") (name "Net-(IC3A-X3)") (class "Default")
      (node (ref "IC3") (pin "12") (pinfunction "X3_12") (pintype "bidirectional"))
      (node (ref "IC8") (pin "10") (pinfunction "Q4_10") (pintype "output"))
    )
    (net (code "48") (name "Net-(IC3A-X4)") (class "Default")
      (node (ref "IC3") (pin "1") (pinfunction "X4_1") (pintype "bidirectional"))
      (node (ref "IC8") (pin "1") (pinfunction "Q5_1") (pintype "output"))
    )
    (net (code "49") (name "Net-(IC3A-X5)") (class "Default")
      (node (ref "IC3") (pin "5") (pinfunction "X5_5") (pintype "bidirectional"))
      (node (ref "IC8") (pin "5") (pinfunction "Q6_5") (pintype "output"))
    )
    (net (code "50") (name "Net-(IC3A-X6)") (class "Default")
      (node (ref "IC3") (pin "2") (pinfunction "X6_2") (pintype "bidirectional"))
      (node (ref "IC8") (pin "6") (pinfunction "Q7_6") (pintype "output"))
    )
    (net (code "51") (name "Net-(IC3A-X7)") (class "Default")
      (node (ref "IC3") (pin "4") (pinfunction "X7_4") (pintype "bidirectional"))
      (node (ref "IC8") (pin "9") (pinfunction "Q8_9") (pintype "output"))
    )
    (net (code "52") (name "Net-(IC4-CIN+{slash}ICSPDAT{slash}AN0{slash}RA0)") (class "Default")
      (node (ref "IC4") (pin "13") (pinfunction "CIN+/ICSPDAT/AN0/RA0_13") (pintype "bidirectional"))
      (node (ref "JP1") (pin "4") (pinfunction "4_4") (pintype "passive"))
    )
    (net (code "53") (name "Net-(IC4-CIN-{slash}VREF{slash}ICSPCLK{slash}AN1{slash}RA1)") (class "Default")
      (node (ref "IC4") (pin "12") (pinfunction "CIN-/VREF/ICSPCLK/AN1/RA1_12") (pintype "bidirectional"))
      (node (ref "JP1") (pin "5") (pinfunction "5_5") (pintype "passive"))
    )
    (net (code "54") (name "Net-(IC4-VPP{slash}MCLR{slash}RA3)") (class "Default")
      (node (ref "IC4") (pin "4") (pinfunction "VPP/MCLR/RA3_4") (pintype "input"))
      (node (ref "JP1") (pin "1") (pinfunction "1_1") (pintype "passive"))
      (node (ref "R3") (pin "2") (pinfunction "2_2") (pintype "passive"))
    )
    (net (code "55") (name "Net-(IC5A--IN)") (class "Default")
      (node (ref "IC5") (pin "1") (pinfunction "OUT_1") (pintype "output"))
      (node (ref "IC5") (pin "2") (pinfunction "-IN_2") (pintype "input"))
      (node (ref "R4") (pin "2") (pinfunction "2_2") (pintype "passive"))
    )
    (net (code "56") (name "Net-(IC5B--IN)") (class "Default")
      (node (ref "D3") (pin "C") (pinfunction "C_C") (pintype "passive"))
      (node (ref "IC5") (pin "6") (pinfunction "-IN_6") (pintype "input"))
      (node (ref "R4") (pin "1") (pinfunction "1_1") (pintype "passive"))
      (node (ref "R5") (pin "2") (pinfunction "2_2") (pintype "passive"))
    )
    (net (code "57") (name "Net-(IC5B-OUT)") (class "Default")
      (node (ref "D3") (pin "A") (pinfunction "A_A") (pintype "passive"))
      (node (ref "IC5") (pin "7") (pinfunction "OUT_7") (pintype "output"))
      (node (ref "Q1") (pin "2") (pinfunction "B_2") (pintype "passive"))
    )
    (net (code "58") (name "Net-(IC6C--IN)") (class "Default")
      (node (ref "IC6") (pin "9") (pinfunction "-IN_9") (pintype "input"))
      (node (ref "R23") (pin "2") (pinfunction "2_2") (pintype "passive"))
      (node (ref "R24") (pin "2") (pinfunction "2_2") (pintype "passive"))
    )
    (net (code "59") (name "Net-(IC6D--IN)") (class "Default")
      (node (ref "C10") (pin "+") (pinfunction "+_+") (pintype "passive"))
      (node (ref "IC6") (pin "13") (pinfunction "-IN_13") (pintype "input"))
      (node (ref "IC6") (pin "14") (pinfunction "OUT_14") (pintype "output"))
    )
    (net (code "60") (name "Net-(IC7A-RES)") (class "Default")
      (node (ref "D7") (pin "C") (pinfunction "C_C") (pintype "passive"))
      (node (ref "IC7") (pin "15") (pinfunction "RES_15") (pintype "input"))
      (node (ref "R25") (pin "2") (pinfunction "2_2") (pintype "passive"))
    )
    (net (code "61") (name "Net-(IC8A-RES)") (class "Default")
      (node (ref "D8") (pin "C") (pinfunction "C_C") (pintype "passive"))
      (node (ref "IC8") (pin "15") (pinfunction "RES_15") (pintype "input"))
      (node (ref "R27") (pin "2") (pinfunction "2_2") (pintype "passive"))
    )
    (net (code "62") (name "Net-(IC9A-I0)") (class "Default")
      (node (ref "IC9") (pin "1") (pinfunction "I0_1") (pintype "input"))
      (node (ref "IC9") (pin "10") (pinfunction "O_10") (pintype "output"))
    )
    (net (code "63") (name "Net-(IC9A-I1)") (class "Default")
      (node (ref "IC9") (pin "11") (pinfunction "O_11") (pintype "output"))
      (node (ref "IC9") (pin "2") (pinfunction "I1_2") (pintype "input"))
      (node (ref "IC9") (pin "5") (pinfunction "I0_5") (pintype "input"))
      (node (ref "IC9") (pin "6") (pinfunction "I1_6") (pintype "input"))
    )
    (net (code "64") (name "Net-(IC10A-B)") (class "Default")
      (node (ref "IC10") (pin "7") (pinfunction "B_7") (pintype "passive"))
      (node (ref "IC10") (pin "8") (pinfunction "E_8") (pintype "passive"))
    )
    (net (code "65") (name "Net-(IC10B-B)") (class "Default")
      (node (ref "IC10") (pin "10") (pinfunction "B_10") (pintype "passive"))
      (node (ref "IC10") (pin "9") (pinfunction "E_9") (pintype "passive"))
    )
    (net (code "66") (name "Net-(IC10C-IN_N)") (class "Default")
      (node (ref "IC10") (pin "4") (pinfunction "IN_N_4") (pintype "input"))
      (node (ref "R11") (pin "1") (pinfunction "1_1") (pintype "passive"))
      (node (ref "R9") (pin "1") (pinfunction "1_1") (pintype "passive"))
    )
    (net (code "67") (name "Net-(IC10C-IN_P)") (class "Default")
      (node (ref "IC10") (pin "3") (pinfunction "IN_P_3") (pintype "input"))
      (node (ref "R10") (pin "1") (pinfunction "1_1") (pintype "passive"))
      (node (ref "R8") (pin "1") (pinfunction "1_1") (pintype "passive"))
    )
    (net (code "68") (name "Net-(IC10C-I_BIAS)") (class "Default")
      (node (ref "IC10") (pin "1") (pinfunction "I_BIAS_1") (pintype "input"))
      (node (ref "R7") (pin "1") (pinfunction "1_1") (pintype "passive"))
    )
    (net (code "69") (name "Net-(IC10C-OUT)") (class "Default")
      (node (ref "IC10") (pin "5") (pinfunction "OUT_5") (pintype "output"))
      (node (ref "IC5") (pin "13") (pinfunction "-IN_13") (pintype "input"))
      (node (ref "R12") (pin "2") (pinfunction "2_2") (pintype "passive"))
      (node (ref "TR1") (pin "1") (pinfunction "1_1") (pintype "passive"))
      (node (ref "TR1") (pin "2") (pinfunction "2_2") (pintype "passive"))
    )
    (net (code "70") (name "Net-(Q1-C)") (class "Default")
      (node (ref "Q1") (pin "1") (pinfunction "C_1") (pintype "passive"))
      (node (ref "R7") (pin "2") (pinfunction "2_2") (pintype "passive"))
    )
    (net (code "71") (name "Net-(Q1-E)") (class "Default")
      (node (ref "Q1") (pin "3") (pinfunction "E_3") (pintype "passive"))
      (node (ref "R5") (pin "1") (pinfunction "1_1") (pintype "passive"))
      (node (ref "R6") (pin "2") (pinfunction "2_2") (pintype "passive"))
    )
    (net (code "72") (name "Net-(Q2-PadE)") (class "Default")
      (node (ref "Q2") (pin "E") (pinfunction "E_E") (pintype "passive"))
      (node (ref "Q3") (pin "B") (pinfunction "B_B") (pintype "passive"))
      (node (ref "R14") (pin "1") (pinfunction "1_1") (pintype "passive"))
    )
    (net (code "73") (name "Net-(Q4-PadC)") (class "Default")
      (node (ref "Q4") (pin "C") (pinfunction "C_C") (pintype "passive"))
      (node (ref "Q5") (pin "B") (pinfunction "B_B") (pintype "passive"))
      (node (ref "R18") (pin "2") (pinfunction "2_2") (pintype "passive"))
    )
    (net (code "74") (name "Net-(Q4-PadE)") (class "Default")
      (node (ref "Q4") (pin "E") (pinfunction "E_E") (pintype "passive"))
      (node (ref "Q5") (pin "E") (pinfunction "E_E") (pintype "passive"))
      (node (ref "R19") (pin "1") (pinfunction "1_1") (pintype "passive"))
    )
    (net (code "75") (name "Net-(Q5-PadC)") (class "Default")
      (node (ref "Q5") (pin "C") (pinfunction "C_C") (pintype "passive"))
      (node (ref "R20") (pin "2") (pinfunction "2_2") (pintype "passive"))
      (node (ref "R21") (pin "1") (pinfunction "1_1") (pintype "passive"))
    )
    (net (code "76") (name "Net-(Q6-PadB)") (class "Default")
      (node (ref "Q6") (pin "B") (pinfunction "B_B") (pintype "passive"))
      (node (ref "R21") (pin "2") (pinfunction "2_2") (pintype "passive"))
    )
    (net (code "77") (name "Net-(R13-Pad2)") (class "Default")
      (node (ref "R13") (pin "2") (pinfunction "2_2") (pintype "passive"))
      (node (ref "TR2") (pin "E") (pinfunction "E_E") (pintype "passive"))
      (node (ref "TR2") (pin "S") (pinfunction "S_S") (pintype "passive"))
    )
    (net (code "78") (name "Net-(X2A-KL)") (class "Default")
      (node (ref "D2") (pin "C") (pinfunction "C_C") (pintype "passive"))
      (node (ref "X2") (pin "1") (pinfunction "KL_1") (pintype "passive"))
      (node (ref "X2") (pin "2") (pinfunction "KL_2") (pintype "passive"))
    )
    (net (code "79") (name "Net-(X2B-KL)") (class "Default")
      (node (ref "D1") (pin "A") (pinfunction "A_A") (pintype "passive"))
      (node (ref "X2") (pin "10") (pinfunction "KL_10") (pintype "passive"))
      (node (ref "X2") (pin "9") (pinfunction "KL_9") (pintype "passive"))
    )
    (net (code "80") (name "unconnected-(IC1B-O-Pad4)") (class "Default")
      (node (ref "IC1") (pin "4") (pinfunction "O_4") (pintype "output"))
    )
    (net (code "81") (name "unconnected-(IC1C-O-Pad6)") (class "Default")
      (node (ref "IC1") (pin "6") (pinfunction "O_6") (pintype "output"))
    )
    (net (code "82") (name "unconnected-(IC1D-O-Pad8)") (class "Default")
      (node (ref "IC1") (pin "8") (pinfunction "O_8") (pintype "output"))
    )
    (net (code "83") (name "unconnected-(IC1E-O-Pad10)") (class "Default")
      (node (ref "IC1") (pin "10") (pinfunction "O_10") (pintype "output"))
    )
    (net (code "84") (name "unconnected-(IC1F-O-Pad12)") (class "Default")
      (node (ref "IC1") (pin "12") (pinfunction "O_12") (pintype "output"))
    )
    (net (code "85") (name "unconnected-(IC4-COUT{slash}T0CKI{slash}INT{slash}AN2{slash}RA2-Pad11)") (class "Default")
      (node (ref "IC4") (pin "11") (pinfunction "COUT/T0CKI/INT/AN2/RA2_11") (pintype "bidirectional"))
    )
    (net (code "86") (name "unconnected-(IC7A-CO-Pad12)") (class "Default")
      (node (ref "IC7") (pin "12") (pinfunction "CO_12") (pintype "output"))
    )
    (net (code "87") (name "unconnected-(IC8A-CO-Pad12)") (class "Default")
      (node (ref "IC8") (pin "12") (pinfunction "CO_12") (pintype "output"))
    )
    (net (code "88") (name "unconnected-(IC8A-Q9-Pad11)") (class "Default")
      (node (ref "IC8") (pin "11") (pinfunction "Q9_11") (pintype "output"))
    )
    (net (code "89") (name "unconnected-(IC10C-I_DIODE-Pad2)") (class "Default")
      (node (ref "IC10") (pin "2") (pinfunction "I_DIODE_2") (pintype "input"))
    )
    (net (code "90") (name "unconnected-(IC10D-I_DIODE-Pad15)") (class "Default")
      (node (ref "IC10") (pin "15") (pinfunction "I_DIODE_15") (pintype "input"))
    )
    (net (code "91") (name "unconnected-(IC10D-OUT-Pad12)") (class "Default")
      (node (ref "IC10") (pin "12") (pinfunction "OUT_12") (pintype "output"))
    )
    (net (code "92") (name "unconnected-(JP1-Pad6)") (class "Default")
      (node (ref "JP1") (pin "6") (pinfunction "6_6") (pintype "passive"))
    )
    (net (code "93") (name "unconnected-(JP2-Pad5)") (class "Default")
      (node (ref "JP2") (pin "5") (pinfunction "5_5") (pintype "passive"))
    )
    (net (code "94") (name "unconnected-(JP2-Pad8)") (class "Default")
      (node (ref "JP2") (pin "8") (pinfunction "8_8") (pintype "passive"))
    )
    (net (code "95") (name "unconnected-(JP2-Pad10)") (class "Default")
      (node (ref "JP2") (pin "10") (pinfunction "10_10") (pintype "passive"))
    )
    (net (code "96") (name "unconnected-(JP2-Pad11)") (class "Default")
      (node (ref "JP2") (pin "11") (pinfunction "11_11") (pintype "passive"))
    )
    (net (code "97") (name "unconnected-(JP2-Pad12)") (class "Default")
      (node (ref "JP2") (pin "12") (pinfunction "12_12") (pintype "passive"))
    )
    (net (code "98") (name "unconnected-(JP2-Pad13)") (class "Default")
      (node (ref "JP2") (pin "13") (pinfunction "13_13") (pintype "passive"))
    )
    (net (code "99") (name "unconnected-(JP2-Pad14)") (class "Default")
      (node (ref "JP2") (pin "14") (pinfunction "14_14") (pintype "passive"))
    )
    (net (code "100") (name "unconnected-(JP2-Pad16)") (class "Default")
      (node (ref "JP2") (pin "16") (pinfunction "16_16") (pintype "passive"))
    )
    (net (code "101") (name "unconnected-(JP2-Pad17)") (class "Default")
      (node (ref "JP2") (pin "17") (pinfunction "17_17") (pintype "passive"))
    )
    (net (code "102") (name "unconnected-(JP2-Pad18)") (class "Default")
      (node (ref "JP2") (pin "18") (pinfunction "18_18") (pintype "passive"))
    )
    (net (code "103") (name "unconnected-(JP3-Pad3)") (class "Default")
      (node (ref "JP3") (pin "3") (pinfunction "3_3") (pintype "passive"))
    )
    (net (code "104") (name "unconnected-(JP3-Pad4)") (class "Default")
      (node (ref "JP3") (pin "4") (pinfunction "4_4") (pintype "passive"))
    )
    (net (code "105") (name "unconnected-(JP3-Pad6)") (class "Default")
      (node (ref "JP3") (pin "6") (pinfunction "6_6") (pintype "passive"))
    )
    (net (code "106") (name "unconnected-(JP3-Pad15)") (class "Default")
      (node (ref "JP3") (pin "15") (pinfunction "15_15") (pintype "passive"))
    )
    (net (code "107") (name "unconnected-(JP3-Pad19)") (class "Default")
      (node (ref "JP3") (pin "19") (pinfunction "19_19") (pintype "passive"))
    )
  )
)
